# TSOC_PSoC4L_R0_0.net
KiCad netlist of a schematic drawn in EAGLE
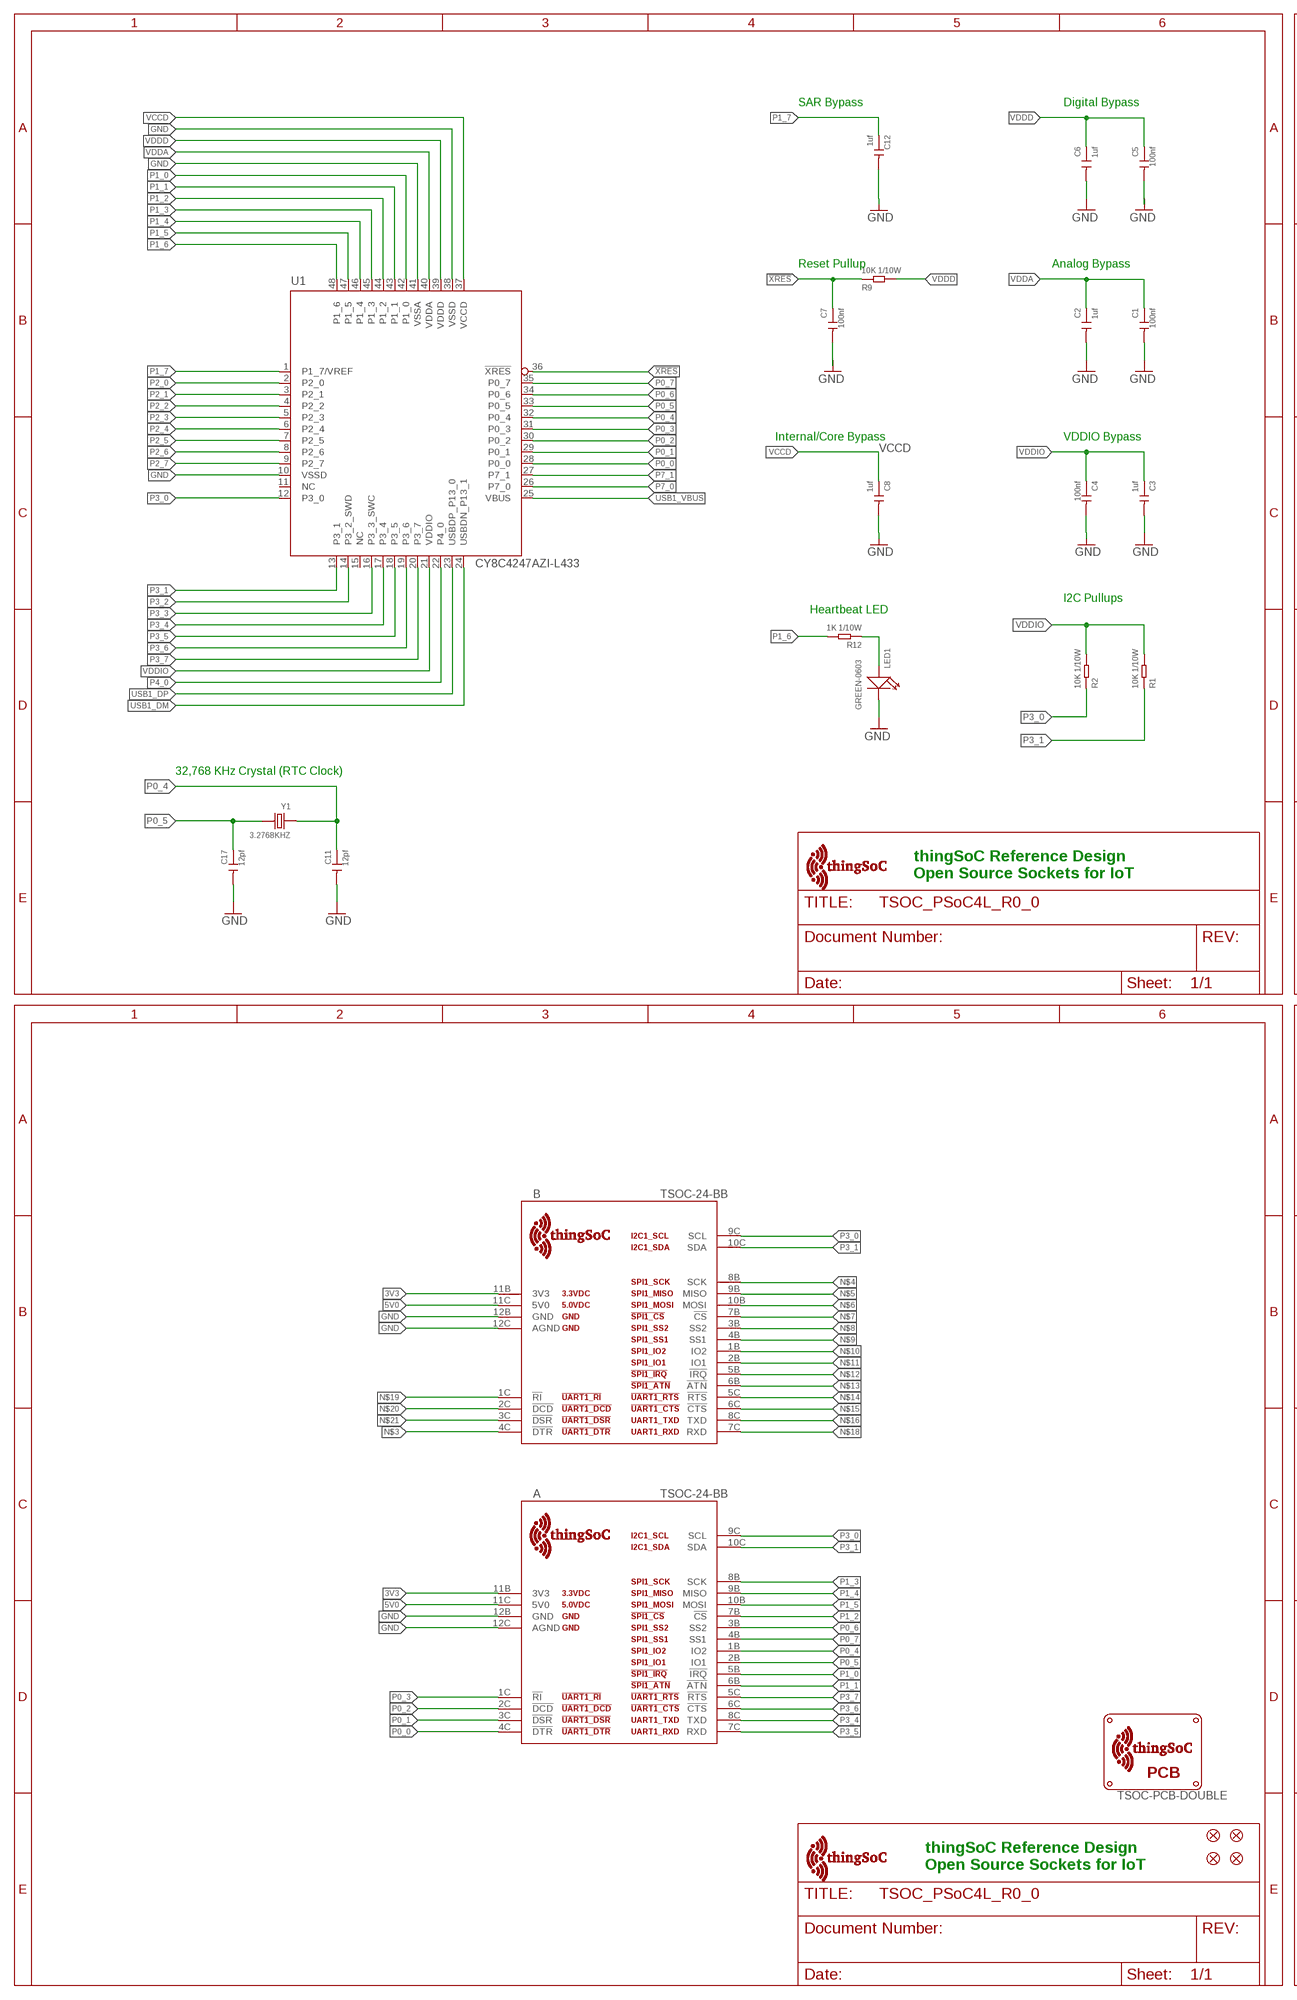
[diagram p0: schematic, sheet 1, part 1 of 2]
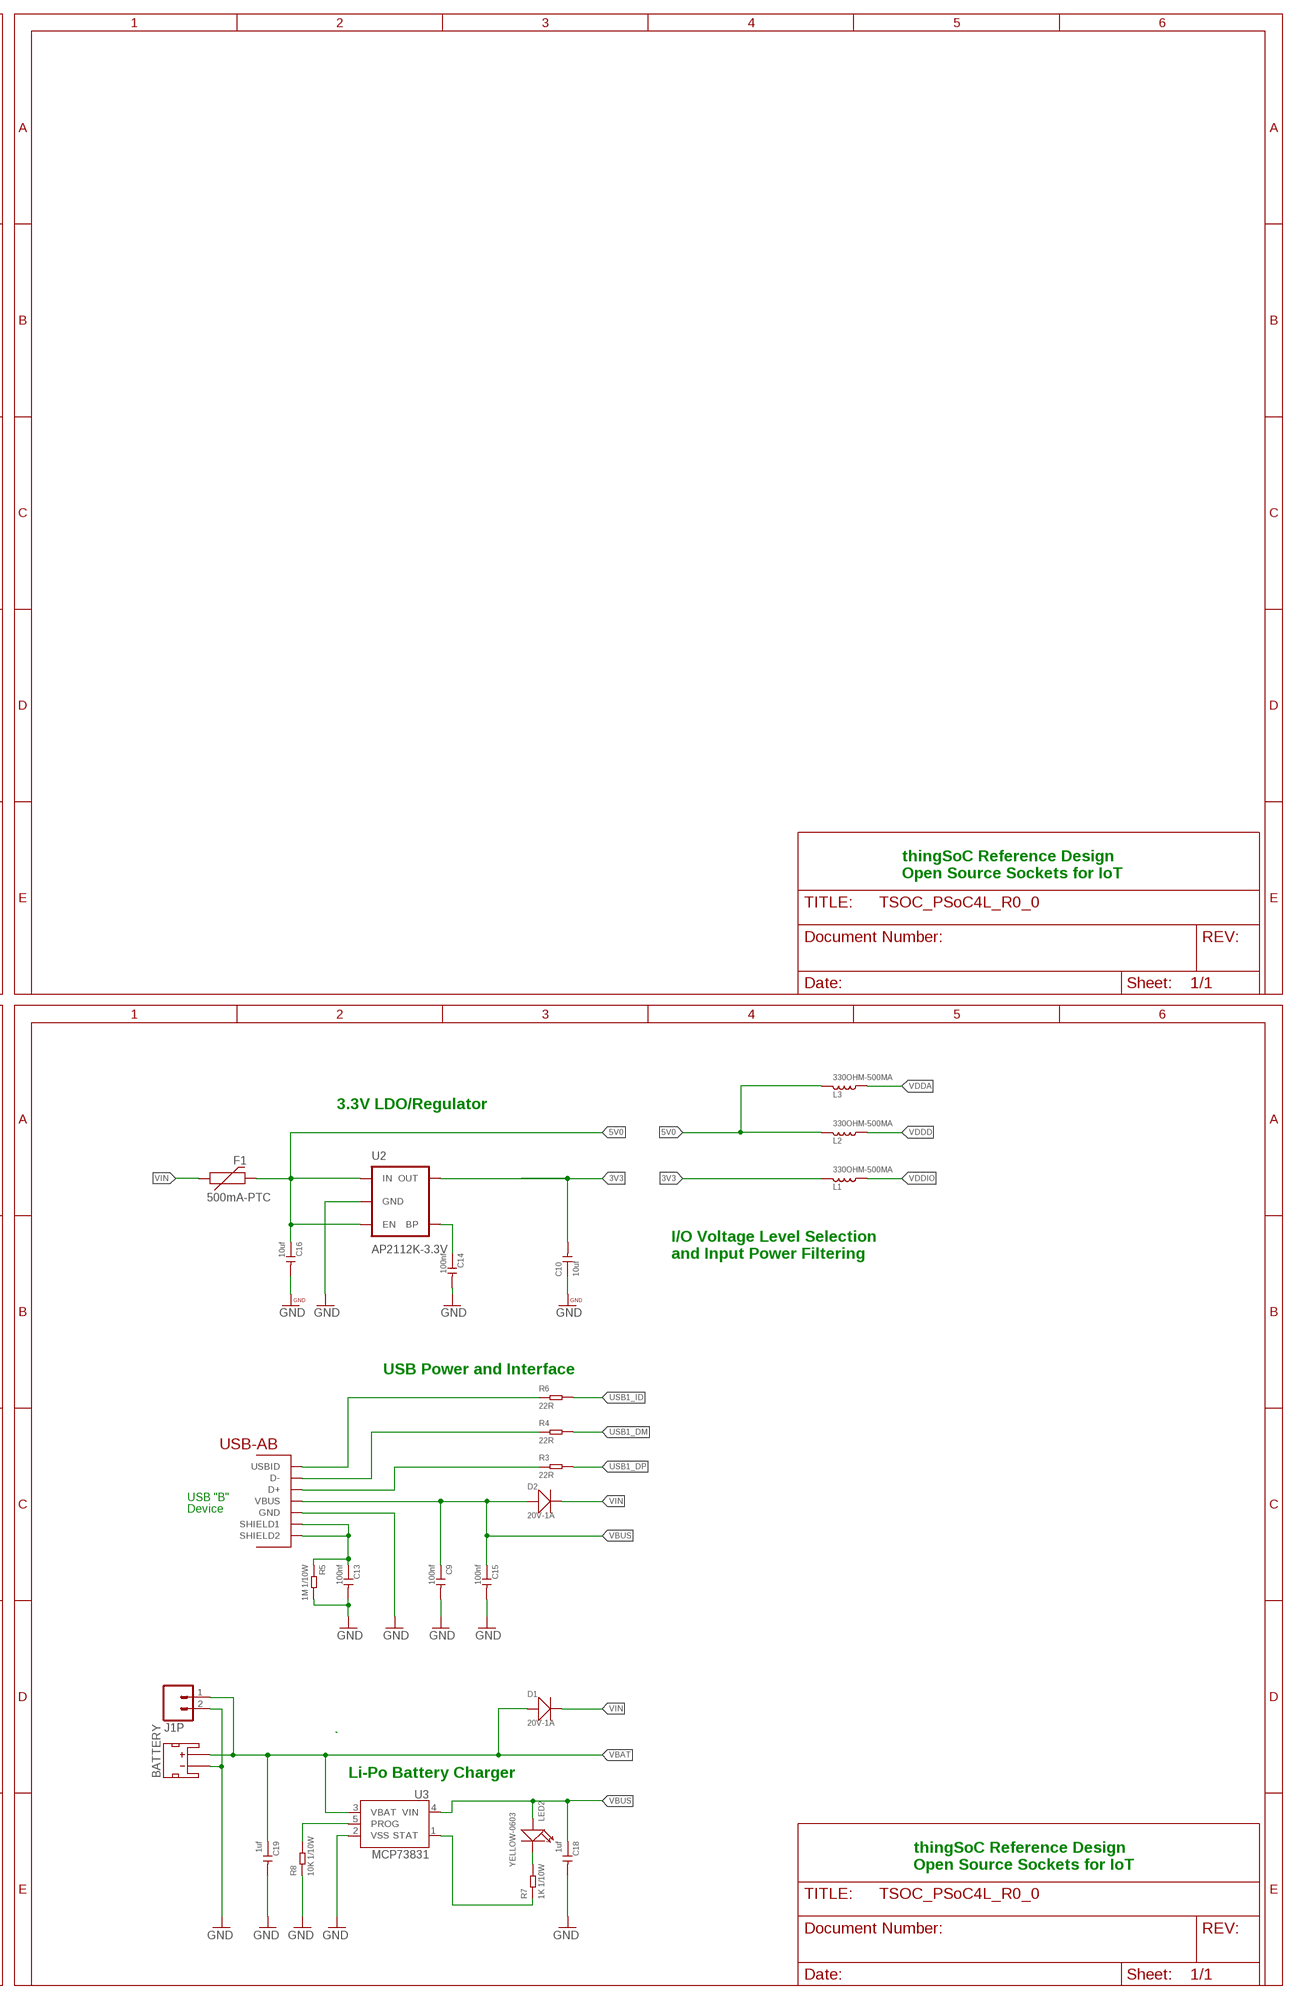
[diagram p1: schematic, sheet 1, part 2 of 2]

(export (version "E")
  (design (tool "Eeschema 10.0.6"))
  (components
    (comp (ref "A")
      (value "TSOC-24-BB")
      (footprint "eagle-import:TSOC-BB-S24")
      (libsource (lib "eagle-import") (part "TSOC-24-BB"))
    )
    (comp (ref "B")
      (value "TSOC-24-BB")
      (footprint "eagle-import:TSOC-BB-S24")
      (libsource (lib "eagle-import") (part "TSOC-24-BB"))
    )
    (comp (ref "BATTERY")
      (value "JST_2MM_MALE")
      (footprint "eagle-import:JST-2-SMD")
      (libsource (lib "eagle-import") (part "JST_2MM_MALE"))
    )
    (comp (ref "C1")
      (value "100nf")
      (footprint "eagle-import:C0603")
      (fields (field (name "MPN") "CC0603KRX7R9BB104"))
      (libsource (lib "eagle-import") (part "CERAMIC-100NF-50V-10%-X7R(0603)"))
    )
    (comp (ref "C2")
      (value "1uf")
      (footprint "eagle-import:C0603")
      (fields (field (name "MPN") "CC0603KRX7R8BB105"))
      (libsource (lib "eagle-import") (part "CERAMIC-1UF-25V-10%-X7R(0603)"))
    )
    (comp (ref "C3")
      (value "1uf")
      (footprint "eagle-import:C0603")
      (fields (field (name "MPN") "CC0603KRX7R8BB105"))
      (libsource (lib "eagle-import") (part "CERAMIC-1UF-25V-10%-X7R(0603)"))
    )
    (comp (ref "C4")
      (value "100nf")
      (footprint "eagle-import:C0603")
      (fields (field (name "MPN") "CC0603KRX7R9BB104"))
      (libsource (lib "eagle-import") (part "CERAMIC-100NF-50V-10%-X7R(0603)"))
    )
    (comp (ref "C5")
      (value "100nf")
      (footprint "eagle-import:C0603")
      (fields (field (name "MPN") "CC0603KRX7R9BB104"))
      (libsource (lib "eagle-import") (part "CERAMIC-100NF-50V-10%-X7R(0603)"))
    )
    (comp (ref "C6")
      (value "1uf")
      (footprint "eagle-import:C0603")
      (fields (field (name "MPN") "CC0603KRX7R8BB105"))
      (libsource (lib "eagle-import") (part "CERAMIC-1UF-25V-10%-X7R(0603)"))
    )
    (comp (ref "C7")
      (value "100nf")
      (footprint "eagle-import:C0603")
      (fields (field (name "MPN") "CC0603KRX7R9BB104"))
      (libsource (lib "eagle-import") (part "CERAMIC-100NF-50V-10%-X7R(0603)"))
    )
    (comp (ref "C8")
      (value "1uf")
      (footprint "eagle-import:C0603")
      (fields (field (name "MPN") "CC0603KRX7R8BB105"))
      (libsource (lib "eagle-import") (part "CERAMIC-1UF-25V-10%-X7R(0603)"))
    )
    (comp (ref "C9")
      (value "100nf")
      (footprint "eagle-import:C0603")
      (fields (field (name "MPN") "CC0603KRX7R9BB104"))
      (libsource (lib "eagle-import") (part "CERAMIC-100NF-50V-10%-X7R(0603)"))
    )
    (comp (ref "C10")
      (value "10uf")
      (footprint "eagle-import:C0603")
      (fields (field (name "MPN") "CC0603KRX5R6BB106"))
      (libsource (lib "eagle-import") (part "CERAMIC-10UF-10V-10%-X5R(0603)"))
    )
    (comp (ref "C11")
      (value "12pf")
      (footprint "eagle-import:C0603")
      (fields (field (name "MPN") "CC0603JRNPO9BN120"))
      (libsource (lib "eagle-import") (part "CERAMIC-12PF-50V-5%-NPO(0603)"))
    )
    (comp (ref "C12")
      (value "1uf")
      (footprint "eagle-import:C0603")
      (fields (field (name "MPN") "CC0603KRX7R8BB105"))
      (libsource (lib "eagle-import") (part "CERAMIC-1UF-25V-10%-X7R(0603)"))
    )
    (comp (ref "C13")
      (value "100nf")
      (footprint "eagle-import:C0603")
      (fields (field (name "MPN") "CC0603KRX7R9BB104"))
      (libsource (lib "eagle-import") (part "CERAMIC-100NF-50V-10%-X7R(0603)"))
    )
    (comp (ref "C14")
      (value "100nf")
      (footprint "eagle-import:C0603")
      (fields (field (name "MPN") "CC0603KRX7R9BB104"))
      (libsource (lib "eagle-import") (part "CERAMIC-100NF-50V-10%-X7R(0603)"))
    )
    (comp (ref "C15")
      (value "100nf")
      (footprint "eagle-import:C0603")
      (fields (field (name "MPN") "CC0603KRX7R9BB104"))
      (libsource (lib "eagle-import") (part "CERAMIC-100NF-50V-10%-X7R(0603)"))
    )
    (comp (ref "C16")
      (value "10uf")
      (footprint "eagle-import:C0603")
      (fields (field (name "MPN") "CC0603KRX5R6BB106"))
      (libsource (lib "eagle-import") (part "CERAMIC-10UF-10V-10%-X5R(0603)"))
    )
    (comp (ref "C17")
      (value "12pf")
      (footprint "eagle-import:C0603")
      (fields (field (name "MPN") "CC0603JRNPO9BN120"))
      (libsource (lib "eagle-import") (part "CERAMIC-12PF-50V-5%-NPO(0603)"))
    )
    (comp (ref "C18")
      (value "1uf")
      (footprint "eagle-import:C0603")
      (fields (field (name "MPN") "CC0603KRX7R8BB105"))
      (libsource (lib "eagle-import") (part "CERAMIC-1UF-25V-10%-X7R(0603)"))
    )
    (comp (ref "C19")
      (value "1uf")
      (footprint "eagle-import:C0603")
      (fields (field (name "MPN") "CC0603KRX7R8BB105"))
      (libsource (lib "eagle-import") (part "CERAMIC-1UF-25V-10%-X7R(0603)"))
    )
    (comp (ref "D1")
      (value "20V-1A")
      (footprint "eagle-import:SOD-123")
      (fields (field (name "MPN") "B5819W"))
      (libsource (lib "eagle-import") (part "SMD-DIODE-SCHOTTKY-20V-1A(SOD-123)"))
    )
    (comp (ref "D2")
      (value "20V-1A")
      (footprint "eagle-import:SOD-123")
      (fields (field (name "MPN") "B5819W"))
      (libsource (lib "eagle-import") (part "SMD-DIODE-SCHOTTKY-20V-1A(SOD-123)"))
    )
    (comp (ref "F1")
      (value "500mA-PTC")
      (footprint "eagle-import:PTC-1206")
      (libsource (lib "eagle-import") (part "PTCSMD"))
    )
    (comp (ref "FID1")
      (value "FIDUCIALUFIDUCIAL")
      (footprint "eagle-import:MICRO-FIDUCIAL")
      (libsource (lib "eagle-import") (part "FIDUCIALUFIDUCIAL"))
    )
    (comp (ref "FID2")
      (value "FIDUCIALUFIDUCIAL")
      (footprint "eagle-import:MICRO-FIDUCIAL")
      (libsource (lib "eagle-import") (part "FIDUCIALUFIDUCIAL"))
    )
    (comp (ref "FID3")
      (value "FIDUCIALUFIDUCIAL")
      (footprint "eagle-import:MICRO-FIDUCIAL")
      (libsource (lib "eagle-import") (part "FIDUCIALUFIDUCIAL"))
    )
    (comp (ref "FID4")
      (value "FIDUCIALUFIDUCIAL")
      (footprint "eagle-import:MICRO-FIDUCIAL")
      (libsource (lib "eagle-import") (part "FIDUCIALUFIDUCIAL"))
    )
    (comp (ref "J1P")
      (value "M02-JST-2-PTH-NO_SILK")
      (footprint "eagle-import:JST-2-PTH-NS")
      (libsource (lib "eagle-import") (part "M02-JST-2-PTH-NO_SILK"))
    )
    (comp (ref "L1")
      (value "330OHM-500MA")
      (footprint "eagle-import:L0603")
      (fields (field (name "MPN") "BLM18AG121SN1D"))
      (libsource (lib "eagle-import") (part "SMD-FERRITE-CHIP-120-OHM-500MA(0603)"))
    )
    (comp (ref "L2")
      (value "330OHM-500MA")
      (footprint "eagle-import:L0603")
      (fields (field (name "MPN") "BLM18AG121SN1D"))
      (libsource (lib "eagle-import") (part "SMD-FERRITE-CHIP-120-OHM-500MA(0603)"))
    )
    (comp (ref "L3")
      (value "330OHM-500MA")
      (footprint "eagle-import:L0603")
      (fields (field (name "MPN") "BLM18AG121SN1D"))
      (libsource (lib "eagle-import") (part "SMD-FERRITE-CHIP-120-OHM-500MA(0603)"))
    )
    (comp (ref "LED1")
      (value "GREEN-0603")
      (footprint "eagle-import:LED-0603")
      (fields (field (name "MPN") "19-217-G7C-AN1P2-3T"))
      (libsource (lib "eagle-import") (part "SMD-LED-CLEAR-GREEN(0603)"))
    )
    (comp (ref "LED2")
      (value "YELLOW-0603")
      (footprint "eagle-import:LED-0603")
      (fields (field (name "MPN") "19-217-Y5C-AM1N1VY-3T"))
      (libsource (lib "eagle-import") (part "SMD-LED-CLEAR-YELLOW(0603)"))
    )
    (comp (ref "R1")
      (value "10K 1/10W")
      (footprint "eagle-import:R0603")
      (fields (field (name "MPN") "RC0603JR-0710KL"))
      (libsource (lib "eagle-import") (part "SMD-RES-10K-5%-1/10W(0603)"))
    )
    (comp (ref "R2")
      (value "10K 1/10W")
      (footprint "eagle-import:R0603")
      (fields (field (name "MPN") "RC0603JR-0710KL"))
      (libsource (lib "eagle-import") (part "SMD-RES-10K-5%-1/10W(0603)"))
    )
    (comp (ref "R3")
      (value "22R")
      (footprint "eagle-import:R0603")
      (fields (field (name "MPN") "RC0603JR-0722RL"))
      (libsource (lib "eagle-import") (part "SMD-RES-22R-5%-1/10W(0603)"))
    )
    (comp (ref "R4")
      (value "22R")
      (footprint "eagle-import:R0603")
      (fields (field (name "MPN") "RC0603JR-0722RL"))
      (libsource (lib "eagle-import") (part "SMD-RES-22R-5%-1/10W(0603)"))
    )
    (comp (ref "R5")
      (value "1M 1/10W")
      (footprint "eagle-import:R0603")
      (fields (field (name "MPN") "RC0603JR-071ML"))
      (libsource (lib "eagle-import") (part "SMD-RES-1M-5%-1/10W(0603)"))
    )
    (comp (ref "R6")
      (value "22R")
      (footprint "eagle-import:R0603")
      (fields (field (name "MPN") "RC0603JR-0722RL"))
      (libsource (lib "eagle-import") (part "SMD-RES-22R-5%-1/10W(0603)"))
    )
    (comp (ref "R7")
      (value "1K 1/10W")
      (footprint "eagle-import:R0603")
      (fields (field (name "MPN") "RC0603JR-071KL"))
      (libsource (lib "eagle-import") (part "SMD-RES-1K-5%-1/10W(0603)"))
    )
    (comp (ref "R8")
      (value "10K 1/10W")
      (footprint "eagle-import:R0603")
      (fields (field (name "MPN") "RC0603JR-0710KL"))
      (libsource (lib "eagle-import") (part "SMD-RES-10K-5%-1/10W(0603)"))
    )
    (comp (ref "R9")
      (value "10K 1/10W")
      (footprint "eagle-import:R0603")
      (fields (field (name "MPN") "RC0603JR-0710KL"))
      (libsource (lib "eagle-import") (part "SMD-RES-10K-5%-1/10W(0603)"))
    )
    (comp (ref "R12")
      (value "1K 1/10W")
      (footprint "eagle-import:R0603")
      (fields (field (name "MPN") "RC0603JR-071KL"))
      (libsource (lib "eagle-import") (part "SMD-RES-1K-5%-1/10W(0603)"))
    )
    (comp (ref "U$1")
      (value "TSOC-PCB-DOUBLE")
      (footprint "eagle-import:TS0C-BB-BRD-DBL-DIM")
      (libsource (lib "eagle-import") (part "TSOC-PCB-DOUBLE"))
    )
    (comp (ref "U$100")
      (value "TSOC-LOGO-SMALL")
      (footprint "eagle-import:TSOC-LOGO-SML")
      (libsource (lib "eagle-import") (part "TSOC-LOGO-SMALL"))
    )
    (comp (ref "U$101")
      (value "TSOC-LOGO-LRG")
      (footprint "eagle-import:TSOC-LOGO-LRG")
      (libsource (lib "eagle-import") (part "TSOC-LOGO-LRG"))
    )
    (comp (ref "U1")
      (value "CY8C4247AZI-L433")
      (footprint "eagle-import:TQFP-7X7-48")
      (libsource (lib "eagle-import") (part "CY8C4247AZI-L433"))
    )
    (comp (ref "U2")
      (value "AP2112K-3.3V")
      (footprint "eagle-import:SOT23-5")
      (libsource (lib "eagle-import") (part "V_REG_LDOSMD"))
    )
    (comp (ref "U3")
      (value "MCP73831")
      (footprint "eagle-import:SOT23-5")
      (libsource (lib "eagle-import") (part "MCP73831"))
    )
    (comp (ref "USB")
      (value "USB_AB")
      (footprint "eagle-import:USB-AB-MICRO-SMD")
      (libsource (lib "eagle-import") (part "USB_AB"))
    )
    (comp (ref "Y1")
      (value "3.2768KHZ")
      (footprint "eagle-import:X2-SMD-L2.0X1.2X0.55MM")
      (fields (field (name "MPN") "FC-12M"))
      (libsource (lib "eagle-import") (part "SMD-CRYSTAL-32.768KHZ-12.5PF-20PPM-90K(2P-L2.0X1.2MM)"))
    )
  )
  (nets
    (net (code "1") (name "/~{XRES}") (class "Default")
      (node (ref "C7") (pin "1") (pinfunction "1_1") (pintype "passive"))
      (node (ref "R9") (pin "1") (pinfunction "1_1") (pintype "passive"))
      (node (ref "U1") (pin "36") (pinfunction "~{XRES}_36") (pintype "bidirectional"))
    )
    (net (code "2") (name "3V3") (class "Default")
      (node (ref "A") (pin "11B") (pinfunction "3V3_11B") (pintype "bidirectional"))
      (node (ref "B") (pin "11B") (pinfunction "3V3_11B") (pintype "bidirectional"))
      (node (ref "C10") (pin "2") (pinfunction "2_2") (pintype "passive"))
      (node (ref "L1") (pin "1") (pinfunction "1_1") (pintype "passive"))
      (node (ref "U2") (pin "5") (pinfunction "OUT_5") (pintype "passive"))
    )
    (net (code "3") (name "5V0") (class "Default")
      (node (ref "A") (pin "11C") (pinfunction "5V0_11C") (pintype "bidirectional"))
      (node (ref "B") (pin "11C") (pinfunction "5V0_11C") (pintype "bidirectional"))
      (node (ref "C16") (pin "1") (pinfunction "1_1") (pintype "passive"))
      (node (ref "F1") (pin "2") (pinfunction "2_2") (pintype "bidirectional"))
      (node (ref "L2") (pin "1") (pinfunction "1_1") (pintype "passive"))
      (node (ref "L3") (pin "1") (pinfunction "1_1") (pintype "passive"))
      (node (ref "U2") (pin "1") (pinfunction "IN_1") (pintype "input"))
      (node (ref "U2") (pin "3") (pinfunction "EN_3") (pintype "input"))
    )
    (net (code "4") (name "GND") (class "Default")
      (node (ref "A") (pin "12B") (pinfunction "GND_12B") (pintype "bidirectional"))
      (node (ref "A") (pin "12C") (pinfunction "AGND_12C") (pintype "bidirectional"))
      (node (ref "B") (pin "12B") (pinfunction "GND_12B") (pintype "bidirectional"))
      (node (ref "B") (pin "12C") (pinfunction "AGND_12C") (pintype "bidirectional"))
      (node (ref "BATTERY") (pin "1") (pinfunction "-_1") (pintype "bidirectional"))
      (node (ref "C1") (pin "2") (pinfunction "2_2") (pintype "passive"))
      (node (ref "C10") (pin "1") (pinfunction "1_1") (pintype "passive"))
      (node (ref "C11") (pin "2") (pinfunction "2_2") (pintype "passive"))
      (node (ref "C12") (pin "2") (pinfunction "2_2") (pintype "passive"))
      (node (ref "C13") (pin "2") (pinfunction "2_2") (pintype "passive"))
      (node (ref "C14") (pin "2") (pinfunction "2_2") (pintype "passive"))
      (node (ref "C15") (pin "2") (pinfunction "2_2") (pintype "passive"))
      (node (ref "C16") (pin "2") (pinfunction "2_2") (pintype "passive"))
      (node (ref "C17") (pin "2") (pinfunction "2_2") (pintype "passive"))
      (node (ref "C18") (pin "2") (pinfunction "2_2") (pintype "passive"))
      (node (ref "C19") (pin "2") (pinfunction "2_2") (pintype "passive"))
      (node (ref "C2") (pin "2") (pinfunction "2_2") (pintype "passive"))
      (node (ref "C3") (pin "2") (pinfunction "2_2") (pintype "passive"))
      (node (ref "C4") (pin "2") (pinfunction "2_2") (pintype "passive"))
      (node (ref "C5") (pin "2") (pinfunction "2_2") (pintype "passive"))
      (node (ref "C6") (pin "2") (pinfunction "2_2") (pintype "passive"))
      (node (ref "C7") (pin "2") (pinfunction "2_2") (pintype "passive"))
      (node (ref "C8") (pin "2") (pinfunction "2_2") (pintype "passive"))
      (node (ref "C9") (pin "2") (pinfunction "2_2") (pintype "passive"))
      (node (ref "J1P") (pin "2") (pinfunction "2_2") (pintype "passive"))
      (node (ref "LED1") (pin "-") (pinfunction "-_-") (pintype "passive"))
      (node (ref "R5") (pin "2") (pinfunction "2_2") (pintype "passive"))
      (node (ref "R8") (pin "1") (pinfunction "1_1") (pintype "passive"))
      (node (ref "U1") (pin "10") (pinfunction "VSSD_10") (pintype "bidirectional"))
      (node (ref "U1") (pin "38") (pinfunction "VSSD_38") (pintype "bidirectional"))
      (node (ref "U1") (pin "41") (pinfunction "VSSA_41") (pintype "bidirectional"))
      (node (ref "U2") (pin "2") (pinfunction "GND_2") (pintype "input"))
      (node (ref "U3") (pin "2") (pinfunction "VSS_2") (pintype "power_in"))
      (node (ref "USB") (pin "GND") (pinfunction "GND_GND") (pintype "bidirectional"))
    )
    (net (code "5") (name "N$3") (class "Default")
      (node (ref "B") (pin "4C") (pinfunction "~{DTR}_4C") (pintype "bidirectional"))
    )
    (net (code "6") (name "N$4") (class "Default")
      (node (ref "B") (pin "8B") (pinfunction "SCK_8B") (pintype "bidirectional"))
    )
    (net (code "7") (name "N$5") (class "Default")
      (node (ref "B") (pin "9B") (pinfunction "MISO_9B") (pintype "bidirectional"))
    )
    (net (code "8") (name "N$6") (class "Default")
      (node (ref "B") (pin "10B") (pinfunction "MOSI_10B") (pintype "bidirectional"))
    )
    (net (code "9") (name "N$7") (class "Default")
      (node (ref "B") (pin "7B") (pinfunction "~{CS}_7B") (pintype "bidirectional"))
    )
    (net (code "10") (name "N$8") (class "Default")
      (node (ref "B") (pin "3B") (pinfunction "SS2_3B") (pintype "bidirectional"))
    )
    (net (code "11") (name "N$9") (class "Default")
      (node (ref "B") (pin "4B") (pinfunction "SS1_4B") (pintype "bidirectional"))
    )
    (net (code "12") (name "N$10") (class "Default")
      (node (ref "B") (pin "1B") (pinfunction "IO2_1B") (pintype "bidirectional"))
    )
    (net (code "13") (name "N$11") (class "Default")
      (node (ref "B") (pin "2B") (pinfunction "IO1_2B") (pintype "bidirectional"))
    )
    (net (code "14") (name "N$12") (class "Default")
      (node (ref "B") (pin "5B") (pinfunction "~{IRQ}_5B") (pintype "bidirectional"))
    )
    (net (code "15") (name "N$13") (class "Default")
      (node (ref "B") (pin "6B") (pinfunction "~{ATN}_6B") (pintype "bidirectional"))
    )
    (net (code "16") (name "N$14") (class "Default")
      (node (ref "B") (pin "5C") (pinfunction "~{RTS}_5C") (pintype "bidirectional"))
    )
    (net (code "17") (name "N$15") (class "Default")
      (node (ref "B") (pin "6C") (pinfunction "~{CTS}_6C") (pintype "bidirectional"))
    )
    (net (code "18") (name "N$16") (class "Default")
      (node (ref "B") (pin "8C") (pinfunction "TXD_8C") (pintype "bidirectional"))
    )
    (net (code "19") (name "N$18") (class "Default")
      (node (ref "B") (pin "7C") (pinfunction "RXD_7C") (pintype "bidirectional"))
    )
    (net (code "20") (name "N$19") (class "Default")
      (node (ref "B") (pin "1C") (pinfunction "~{RI}_1C") (pintype "bidirectional"))
    )
    (net (code "21") (name "N$20") (class "Default")
      (node (ref "B") (pin "2C") (pinfunction "~{DCD}_2C") (pintype "bidirectional"))
    )
    (net (code "22") (name "N$21") (class "Default")
      (node (ref "B") (pin "3C") (pinfunction "~{DSR}_3C") (pintype "bidirectional"))
    )
    (net (code "23") (name "Net-(C13-Pad1)") (class "Default")
      (node (ref "C13") (pin "1") (pinfunction "1_1") (pintype "passive"))
      (node (ref "R5") (pin "1") (pinfunction "1_1") (pintype "passive"))
      (node (ref "USB") (pin "SHIELD1") (pinfunction "SHIELD1_SHIELD1") (pintype "bidirectional"))
      (node (ref "USB") (pin "SHIELD2") (pinfunction "SHIELD2_SHIELD2") (pintype "bidirectional"))
    )
    (net (code "24") (name "Net-(LED1-Pad+)") (class "Default")
      (node (ref "LED1") (pin "+") (pinfunction "+_+") (pintype "passive"))
      (node (ref "R12") (pin "1") (pinfunction "1_1") (pintype "passive"))
    )
    (net (code "25") (name "Net-(LED2-Pad-)") (class "Default")
      (node (ref "LED2") (pin "-") (pinfunction "-_-") (pintype "passive"))
      (node (ref "R7") (pin "2") (pinfunction "2_2") (pintype "passive"))
    )
    (net (code "26") (name "Net-(R3-Pad1)") (class "Default")
      (node (ref "R3") (pin "1") (pinfunction "1_1") (pintype "passive"))
      (node (ref "USB") (pin "D+") (pinfunction "D+_D+") (pintype "bidirectional"))
    )
    (net (code "27") (name "Net-(R4-Pad1)") (class "Default")
      (node (ref "R4") (pin "1") (pinfunction "1_1") (pintype "passive"))
      (node (ref "USB") (pin "D-") (pinfunction "D-_D-") (pintype "bidirectional"))
    )
    (net (code "28") (name "Net-(U2-BP)") (class "Default")
      (node (ref "C14") (pin "1") (pinfunction "1_1") (pintype "passive"))
      (node (ref "U2") (pin "4") (pinfunction "BP_4") (pintype "input"))
    )
    (net (code "29") (name "Net-(U3-PROG)") (class "Default")
      (node (ref "R8") (pin "2") (pinfunction "2_2") (pintype "passive"))
      (node (ref "U3") (pin "5") (pinfunction "PROG_5") (pintype "input"))
    )
    (net (code "30") (name "Net-(U3-STAT)") (class "Default")
      (node (ref "R7") (pin "1") (pinfunction "1_1") (pintype "passive"))
      (node (ref "U3") (pin "1") (pinfunction "STAT_1") (pintype "output"))
    )
    (net (code "31") (name "Net-(USB-USBID)") (class "Default")
      (node (ref "R6") (pin "1") (pinfunction "1_1") (pintype "passive"))
      (node (ref "USB") (pin "ID") (pinfunction "USBID_ID") (pintype "bidirectional"))
    )
    (net (code "32") (name "P0_0") (class "Default")
      (node (ref "A") (pin "4C") (pinfunction "~{DTR}_4C") (pintype "bidirectional"))
      (node (ref "U1") (pin "28") (pinfunction "P0_0_28") (pintype "bidirectional"))
    )
    (net (code "33") (name "P0_1") (class "Default")
      (node (ref "A") (pin "3C") (pinfunction "~{DSR}_3C") (pintype "bidirectional"))
      (node (ref "U1") (pin "29") (pinfunction "P0_1_29") (pintype "bidirectional"))
    )
    (net (code "34") (name "P0_2") (class "Default")
      (node (ref "A") (pin "2C") (pinfunction "~{DCD}_2C") (pintype "bidirectional"))
      (node (ref "U1") (pin "30") (pinfunction "P0_2_30") (pintype "input"))
    )
    (net (code "35") (name "P0_3") (class "Default")
      (node (ref "A") (pin "1C") (pinfunction "~{RI}_1C") (pintype "bidirectional"))
      (node (ref "U1") (pin "31") (pinfunction "P0_3_31") (pintype "bidirectional"))
    )
    (net (code "36") (name "P0_4") (class "Default")
      (node (ref "A") (pin "1B") (pinfunction "IO2_1B") (pintype "bidirectional"))
      (node (ref "C11") (pin "1") (pinfunction "1_1") (pintype "passive"))
      (node (ref "U1") (pin "32") (pinfunction "P0_4_32") (pintype "bidirectional"))
      (node (ref "Y1") (pin "1") (pinfunction "1_1") (pintype "passive"))
    )
    (net (code "37") (name "P0_5") (class "Default")
      (node (ref "A") (pin "2B") (pinfunction "IO1_2B") (pintype "bidirectional"))
      (node (ref "C17") (pin "1") (pinfunction "1_1") (pintype "passive"))
      (node (ref "U1") (pin "33") (pinfunction "P0_5_33") (pintype "bidirectional"))
      (node (ref "Y1") (pin "2") (pinfunction "2_2") (pintype "passive"))
    )
    (net (code "38") (name "P0_6") (class "Default")
      (node (ref "A") (pin "3B") (pinfunction "SS2_3B") (pintype "bidirectional"))
      (node (ref "U1") (pin "34") (pinfunction "P0_6_34") (pintype "power_in"))
    )
    (net (code "39") (name "P0_7") (class "Default")
      (node (ref "A") (pin "4B") (pinfunction "SS1_4B") (pintype "bidirectional"))
      (node (ref "U1") (pin "35") (pinfunction "P0_7_35") (pintype "bidirectional"))
    )
    (net (code "40") (name "P1_0") (class "Default")
      (node (ref "A") (pin "5B") (pinfunction "~{IRQ}_5B") (pintype "bidirectional"))
      (node (ref "U1") (pin "42") (pinfunction "P1_0_42") (pintype "bidirectional"))
    )
    (net (code "41") (name "P1_1") (class "Default")
      (node (ref "A") (pin "6B") (pinfunction "~{ATN}_6B") (pintype "bidirectional"))
      (node (ref "U1") (pin "43") (pinfunction "P1_1_43") (pintype "bidirectional"))
    )
    (net (code "42") (name "P1_2") (class "Default")
      (node (ref "A") (pin "7B") (pinfunction "~{CS}_7B") (pintype "bidirectional"))
      (node (ref "U1") (pin "44") (pinfunction "P1_2_44") (pintype "power_in"))
    )
    (net (code "43") (name "P1_3") (class "Default")
      (node (ref "A") (pin "8B") (pinfunction "SCK_8B") (pintype "bidirectional"))
      (node (ref "U1") (pin "45") (pinfunction "P1_3_45") (pintype "bidirectional"))
    )
    (net (code "44") (name "P1_4") (class "Default")
      (node (ref "A") (pin "9B") (pinfunction "MISO_9B") (pintype "bidirectional"))
      (node (ref "U1") (pin "46") (pinfunction "P1_4_46") (pintype "bidirectional"))
    )
    (net (code "45") (name "P1_5") (class "Default")
      (node (ref "A") (pin "10B") (pinfunction "MOSI_10B") (pintype "bidirectional"))
      (node (ref "U1") (pin "47") (pinfunction "P1_5_47") (pintype "bidirectional"))
    )
    (net (code "46") (name "P1_6") (class "Default")
      (node (ref "R12") (pin "2") (pinfunction "2_2") (pintype "passive"))
      (node (ref "U1") (pin "48") (pinfunction "P1_6_48") (pintype "bidirectional"))
    )
    (net (code "47") (name "P1_7") (class "Default")
      (node (ref "C12") (pin "1") (pinfunction "1_1") (pintype "passive"))
      (node (ref "U1") (pin "1") (pinfunction "P1_7/VREF_1") (pintype "bidirectional"))
    )
    (net (code "48") (name "P2_0") (class "Default")
      (node (ref "U1") (pin "2") (pinfunction "P2_0_2") (pintype "bidirectional"))
    )
    (net (code "49") (name "P2_1") (class "Default")
      (node (ref "U1") (pin "3") (pinfunction "P2_1_3") (pintype "bidirectional"))
    )
    (net (code "50") (name "P2_2") (class "Default")
      (node (ref "U1") (pin "4") (pinfunction "P2_2_4") (pintype "power_in"))
    )
    (net (code "51") (name "P2_3") (class "Default")
      (node (ref "U1") (pin "5") (pinfunction "P2_3_5") (pintype "bidirectional"))
    )
    (net (code "52") (name "P2_4") (class "Default")
      (node (ref "U1") (pin "6") (pinfunction "P2_4_6") (pintype "bidirectional"))
    )
    (net (code "53") (name "P2_5") (class "Default")
      (node (ref "U1") (pin "7") (pinfunction "P2_5_7") (pintype "bidirectional"))
    )
    (net (code "54") (name "P2_6") (class "Default")
      (node (ref "U1") (pin "8") (pinfunction "P2_6_8") (pintype "power_in"))
    )
    (net (code "55") (name "P2_7") (class "Default")
      (node (ref "U1") (pin "9") (pinfunction "P2_7_9") (pintype "bidirectional"))
    )
    (net (code "56") (name "P3_0") (class "Default")
      (node (ref "A") (pin "9C") (pinfunction "SCL_9C") (pintype "bidirectional"))
      (node (ref "B") (pin "9C") (pinfunction "SCL_9C") (pintype "bidirectional"))
      (node (ref "R2") (pin "1") (pinfunction "1_1") (pintype "passive"))
      (node (ref "U1") (pin "12") (pinfunction "P3_0_12") (pintype "bidirectional"))
    )
    (net (code "57") (name "P3_1") (class "Default")
      (node (ref "A") (pin "10C") (pinfunction "SDA_10C") (pintype "bidirectional"))
      (node (ref "B") (pin "10C") (pinfunction "SDA_10C") (pintype "bidirectional"))
      (node (ref "R1") (pin "1") (pinfunction "1_1") (pintype "passive"))
      (node (ref "U1") (pin "13") (pinfunction "P3_1_13") (pintype "bidirectional"))
    )
    (net (code "58") (name "P3_2") (class "Default")
      (node (ref "U1") (pin "14") (pinfunction "P3_2_SWD_14") (pintype "bidirectional"))
    )
    (net (code "59") (name "P3_3") (class "Default")
      (node (ref "U1") (pin "16") (pinfunction "P3_3_SWC_16") (pintype "bidirectional"))
    )
    (net (code "60") (name "P3_4") (class "Default")
      (node (ref "A") (pin "8C") (pinfunction "TXD_8C") (pintype "bidirectional"))
      (node (ref "U1") (pin "17") (pinfunction "P3_4_17") (pintype "bidirectional"))
    )
    (net (code "61") (name "P3_5") (class "Default")
      (node (ref "A") (pin "7C") (pinfunction "RXD_7C") (pintype "bidirectional"))
      (node (ref "U1") (pin "18") (pinfunction "P3_5_18") (pintype "bidirectional"))
    )
    (net (code "62") (name "P3_6") (class "Default")
      (node (ref "A") (pin "6C") (pinfunction "~{CTS}_6C") (pintype "bidirectional"))
      (node (ref "U1") (pin "19") (pinfunction "P3_6_19") (pintype "power_in"))
    )
    (net (code "63") (name "P3_7") (class "Default")
      (node (ref "A") (pin "5C") (pinfunction "~{RTS}_5C") (pintype "bidirectional"))
      (node (ref "U1") (pin "20") (pinfunction "P3_7_20") (pintype "bidirectional"))
    )
    (net (code "64") (name "P4_0") (class "Default")
      (node (ref "U1") (pin "22") (pinfunction "P4_0_22") (pintype "bidirectional"))
    )
    (net (code "65") (name "P7_0") (class "Default")
      (node (ref "U1") (pin "26") (pinfunction "P7_0_26") (pintype "bidirectional"))
    )
    (net (code "66") (name "P7_1") (class "Default")
      (node (ref "U1") (pin "27") (pinfunction "P7_1_27") (pintype "bidirectional"))
    )
    (net (code "67") (name "USB1_DM") (class "Default")
      (node (ref "R4") (pin "2") (pinfunction "2_2") (pintype "passive"))
      (node (ref "U1") (pin "24") (pinfunction "USBDN_P13_1_24") (pintype "bidirectional"))
    )
    (net (code "68") (name "USB1_DP") (class "Default")
      (node (ref "R3") (pin "2") (pinfunction "2_2") (pintype "passive"))
      (node (ref "U1") (pin "23") (pinfunction "USBDP_P13_0_23") (pintype "bidirectional"))
    )
    (net (code "69") (name "USB1_ID") (class "Default")
      (node (ref "R6") (pin "2") (pinfunction "2_2") (pintype "passive"))
    )
    (net (code "70") (name "USB1_VBUS") (class "Default")
      (node (ref "U1") (pin "25") (pinfunction "VBUS_25") (pintype "bidirectional"))
    )
    (net (code "71") (name "VBAT") (class "Default")
      (node (ref "BATTERY") (pin "2") (pinfunction "+_2") (pintype "bidirectional"))
      (node (ref "C19") (pin "1") (pinfunction "1_1") (pintype "passive"))
      (node (ref "D1") (pin "+") (pinfunction "+_+") (pintype "passive"))
      (node (ref "J1P") (pin "1") (pinfunction "1_1") (pintype "passive"))
      (node (ref "U3") (pin "3") (pinfunction "VBAT_3") (pintype "power_in"))
    )
    (net (code "72") (name "VBUS") (class "Default")
      (node (ref "C15") (pin "1") (pinfunction "1_1") (pintype "passive"))
      (node (ref "C18") (pin "1") (pinfunction "1_1") (pintype "passive"))
      (node (ref "C9") (pin "1") (pinfunction "1_1") (pintype "passive"))
      (node (ref "D2") (pin "+") (pinfunction "+_+") (pintype "passive"))
      (node (ref "LED2") (pin "+") (pinfunction "+_+") (pintype "passive"))
      (node (ref "U3") (pin "4") (pinfunction "VIN_4") (pintype "power_in"))
      (node (ref "USB") (pin "VBUS") (pinfunction "VBUS_VBUS") (pintype "bidirectional"))
    )
    (net (code "73") (name "VCCD") (class "Default")
      (node (ref "C8") (pin "1") (pinfunction "1_1") (pintype "passive"))
      (node (ref "U1") (pin "37") (pinfunction "VCCD_37") (pintype "bidirectional"))
    )
    (net (code "74") (name "VDDA") (class "Default")
      (node (ref "C1") (pin "1") (pinfunction "1_1") (pintype "passive"))
      (node (ref "C2") (pin "1") (pinfunction "1_1") (pintype "passive"))
      (node (ref "L3") (pin "2") (pinfunction "2_2") (pintype "passive"))
      (node (ref "U1") (pin "40") (pinfunction "VDDA_40") (pintype "bidirectional"))
    )
    (net (code "75") (name "VDDD") (class "Default")
      (node (ref "C5") (pin "1") (pinfunction "1_1") (pintype "passive"))
      (node (ref "C6") (pin "1") (pinfunction "1_1") (pintype "passive"))
      (node (ref "L2") (pin "2") (pinfunction "2_2") (pintype "passive"))
      (node (ref "R9") (pin "2") (pinfunction "2_2") (pintype "passive"))
      (node (ref "U1") (pin "39") (pinfunction "VDDD_39") (pintype "bidirectional"))
    )
    (net (code "76") (name "VDDIO") (class "Default")
      (node (ref "C3") (pin "1") (pinfunction "1_1") (pintype "passive"))
      (node (ref "C4") (pin "1") (pinfunction "1_1") (pintype "passive"))
      (node (ref "L1") (pin "2") (pinfunction "2_2") (pintype "passive"))
      (node (ref "R1") (pin "2") (pinfunction "2_2") (pintype "passive"))
      (node (ref "R2") (pin "2") (pinfunction "2_2") (pintype "passive"))
      (node (ref "U1") (pin "21") (pinfunction "VDDIO_21") (pintype "bidirectional"))
    )
    (net (code "77") (name "VIN") (class "Default")
      (node (ref "D1") (pin "-") (pinfunction "-_-") (pintype "passive"))
      (node (ref "D2") (pin "-") (pinfunction "-_-") (pintype "passive"))
      (node (ref "F1") (pin "1") (pinfunction "1_1") (pintype "bidirectional"))
    )
    (net (code "78") (name "unconnected-(BATTERY-PAD1-PadNC1)") (class "Default")
      (node (ref "BATTERY") (pin "NC1") (pinfunction "PAD1_NC1") (pintype "bidirectional"))
    )
    (net (code "79") (name "unconnected-(BATTERY-PAD2-PadNC2)") (class "Default")
      (node (ref "BATTERY") (pin "NC2") (pinfunction "PAD2_NC2") (pintype "bidirectional"))
    )
    (net (code "80") (name "unconnected-(U1-NC-Pad11)") (class "Default")
      (node (ref "U1") (pin "11") (pinfunction "NC_11") (pintype "bidirectional"))
    )
    (net (code "81") (name "unconnected-(U1-NC-Pad15)") (class "Default")
      (node (ref "U1") (pin "15") (pinfunction "NC_15") (pintype "bidirectional"))
    )
  )
)
